# SDCARD.net
KiCad netlist of a schematic drawn in Altium Designer
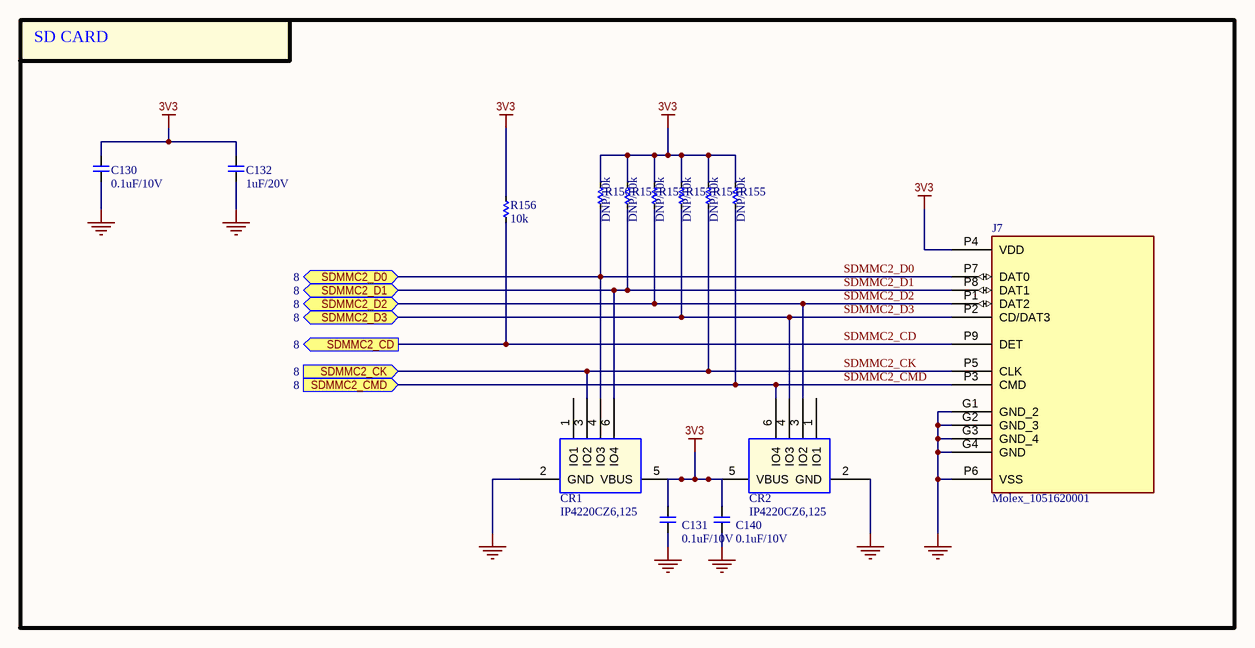
[diagram p0: SDCARD.SchDoc]

(export (version "E")
  (design (tool "Eeschema 10.0.6"))
  (components
    (comp (ref "C130")
      (value "0.1uF/10V")
      (footprint "CAP_C_1005X50_L")
      (description "CAP CHIP")
      (libsource (lib "IFBschelib") (part "_CAP_C_2"))
    )
    (comp (ref "C131")
      (value "0.1uF/10V")
      (footprint "CAP_C_1005X50_L")
      (description "CAP CHIP")
      (libsource (lib "IFBschelib") (part "_CAP_C_2"))
    )
    (comp (ref "C132")
      (value "1uF/20V")
      (footprint "CAP_C_1005X50_L")
      (description "CAP CHIP")
      (libsource (lib "IFBschelib") (part "_CAP_C_2"))
    )
    (comp (ref "C140")
      (value "0.1uF/10V")
      (footprint "CAP_C_1005X50_L")
      (description "CAP CHIP")
      (libsource (lib "IFBschelib") (part "_CAP_C_2"))
    )
    (comp (ref "CR1")
      (value "IP4220CZ6,125")
      (footprint "DIODE_SOT457_1P7X3P1_NEX")
      (description "TVS DIODE 5.5VWM 6TSOP")
      (fields (field (name "COPYRIGHT") "Copyright (C) 2025 Ultra Librarian. All rights reserved."))
      (libsource (lib "") (part "IP4220CZ6,125_1"))
    )
    (comp (ref "CR2")
      (value "IP4220CZ6,125")
      (footprint "DIODE_SOT457_1P7X3P1_NEX")
      (description "TVS DIODE 5.5VWM 6TSOP")
      (fields (field (name "COPYRIGHT") "Copyright (C) 2025 Ultra Librarian. All rights reserved."))
      (libsource (lib "IFBschelib") (part "IP4220CZ6,125"))
    )
    (comp (ref "J7")
      (value "Molex_1051620001")
      (footprint "MOLEX_1051620001")
      (description "9 (8 + 1) Position Card Connector Secure Digital - microSDâ„¢ Surface Mount, Right Angle Gold")
      (fields (field (name "MF") "Molex") (field (name "MP") "1051620001"))
      (libsource (lib "IFBschelib") (part "Molex_1051620001"))
    )
    (comp (ref "R150")
      (value "DNP/10k")
      (footprint "RES_C_1005x30_L")
      (description "RES")
      (libsource (lib "IFBschelib") (part "_RES_B_2"))
    )
    (comp (ref "R151")
      (value "DNP/10k")
      (footprint "RES_C_1005x30_L")
      (description "RES")
      (libsource (lib "IFBschelib") (part "_RES_B_2"))
    )
    (comp (ref "R152")
      (value "DNP/10k")
      (footprint "RES_C_1005x30_L")
      (description "RES")
      (libsource (lib "IFBschelib") (part "_RES_B_2"))
    )
    (comp (ref "R153")
      (value "DNP/10k")
      (footprint "RES_C_1005x30_L")
      (description "RES")
      (libsource (lib "IFBschelib") (part "_RES_B_2"))
    )
    (comp (ref "R154")
      (value "DNP/10k")
      (footprint "RES_C_1005x30_L")
      (description "RES")
      (libsource (lib "IFBschelib") (part "_RES_B_2"))
    )
    (comp (ref "R155")
      (value "DNP/10k")
      (footprint "RES_C_1005x30_L")
      (description "RES")
      (libsource (lib "IFBschelib") (part "_RES_B_2"))
    )
    (comp (ref "R156")
      (value "10k")
      (footprint "RES_C_1005x30_L")
      (description "RES")
      (libsource (lib "IFBschelib") (part "_RES_B_2"))
    )
  )
  (nets
    (net (code "1") (name "/SDMMC2_CD") (class "Default")
      (node (ref "J7") (pin "P9") (pinfunction "DET_P9") (pintype "passive"))
      (node (ref "R156") (pin "1") (pinfunction "1_1") (pintype "passive"))
    )
    (net (code "2") (name "/SDMMC2_CK") (class "Default")
      (node (ref "CR1") (pin "3") (pinfunction "IO2_3") (pintype "passive"))
      (node (ref "J7") (pin "P5") (pinfunction "CLK_P5") (pintype "passive"))
      (node (ref "R154") (pin "1") (pinfunction "1_1") (pintype "passive"))
    )
    (net (code "3") (name "/SDMMC2_CMD") (class "Default")
      (node (ref "CR2") (pin "6") (pinfunction "IO4_6") (pintype "passive"))
      (node (ref "J7") (pin "P3") (pinfunction "CMD_P3") (pintype "passive"))
      (node (ref "R155") (pin "1") (pinfunction "1_1") (pintype "passive"))
    )
    (net (code "4") (name "/SDMMC2_D0") (class "Default")
      (node (ref "CR1") (pin "4") (pinfunction "IO3_4") (pintype "passive"))
      (node (ref "J7") (pin "P7") (pinfunction "DAT0_P7") (pintype "bidirectional"))
      (node (ref "R150") (pin "1") (pinfunction "1_1") (pintype "passive"))
    )
    (net (code "5") (name "/SDMMC2_D1") (class "Default")
      (node (ref "CR1") (pin "6") (pinfunction "IO4_6") (pintype "passive"))
      (node (ref "J7") (pin "P8") (pinfunction "DAT1_P8") (pintype "bidirectional"))
      (node (ref "R151") (pin "1") (pinfunction "1_1") (pintype "passive"))
    )
    (net (code "6") (name "/SDMMC2_D2") (class "Default")
      (node (ref "CR2") (pin "3") (pinfunction "IO2_3") (pintype "passive"))
      (node (ref "J7") (pin "P1") (pinfunction "DAT2_P1") (pintype "bidirectional"))
      (node (ref "R152") (pin "1") (pinfunction "1_1") (pintype "passive"))
    )
    (net (code "7") (name "/SDMMC2_D3") (class "Default")
      (node (ref "CR2") (pin "4") (pinfunction "IO3_4") (pintype "passive"))
      (node (ref "J7") (pin "P2") (pinfunction "CD/DAT3_P2") (pintype "passive"))
      (node (ref "R153") (pin "1") (pinfunction "1_1") (pintype "passive"))
    )
    (net (code "8") (name "3V3") (class "Default")
      (node (ref "C130") (pin "2") (pinfunction "2_2") (pintype "passive"))
      (node (ref "C131") (pin "2") (pinfunction "2_2") (pintype "passive"))
      (node (ref "C132") (pin "2") (pinfunction "2_2") (pintype "passive"))
      (node (ref "C140") (pin "2") (pinfunction "2_2") (pintype "passive"))
      (node (ref "CR1") (pin "5") (pinfunction "VBUS_5") (pintype "passive"))
      (node (ref "CR2") (pin "5") (pinfunction "VBUS_5") (pintype "passive"))
      (node (ref "J7") (pin "P4") (pinfunction "VDD_P4") (pintype "power_in"))
      (node (ref "R150") (pin "2") (pinfunction "2_2") (pintype "passive"))
      (node (ref "R151") (pin "2") (pinfunction "2_2") (pintype "passive"))
      (node (ref "R152") (pin "2") (pinfunction "2_2") (pintype "passive"))
      (node (ref "R153") (pin "2") (pinfunction "2_2") (pintype "passive"))
      (node (ref "R154") (pin "2") (pinfunction "2_2") (pintype "passive"))
      (node (ref "R155") (pin "2") (pinfunction "2_2") (pintype "passive"))
      (node (ref "R156") (pin "2") (pinfunction "2_2") (pintype "passive"))
    )
    (net (code "9") (name "GND") (class "Default")
      (node (ref "C130") (pin "1") (pinfunction "1_1") (pintype "passive"))
      (node (ref "C131") (pin "1") (pinfunction "1_1") (pintype "passive"))
      (node (ref "C132") (pin "1") (pinfunction "1_1") (pintype "passive"))
      (node (ref "C140") (pin "1") (pinfunction "1_1") (pintype "passive"))
      (node (ref "CR1") (pin "2") (pinfunction "GND_2") (pintype "passive"))
      (node (ref "CR2") (pin "2") (pinfunction "GND_2") (pintype "passive"))
      (node (ref "J7") (pin "G1") (pinfunction "GND_2_G1") (pintype "passive"))
      (node (ref "J7") (pin "G2") (pinfunction "GND_3_G2") (pintype "passive"))
      (node (ref "J7") (pin "G3") (pinfunction "GND_4_G3") (pintype "passive"))
      (node (ref "J7") (pin "G4") (pinfunction "GND_G4") (pintype "passive"))
      (node (ref "J7") (pin "P6") (pinfunction "VSS_P6") (pintype "passive"))
    )
    (net (code "10") (name "unconnected-(CR1-IO1-Pad1)") (class "Default")
      (node (ref "CR1") (pin "1") (pinfunction "IO1_1") (pintype "passive"))
    )
    (net (code "11") (name "unconnected-(CR2-IO1-Pad1)") (class "Default")
      (node (ref "CR2") (pin "1") (pinfunction "IO1_1") (pintype "passive"))
    )
  )
)
